# 03_MCU.net
KiCad netlist of a schematic drawn in Altium Designer
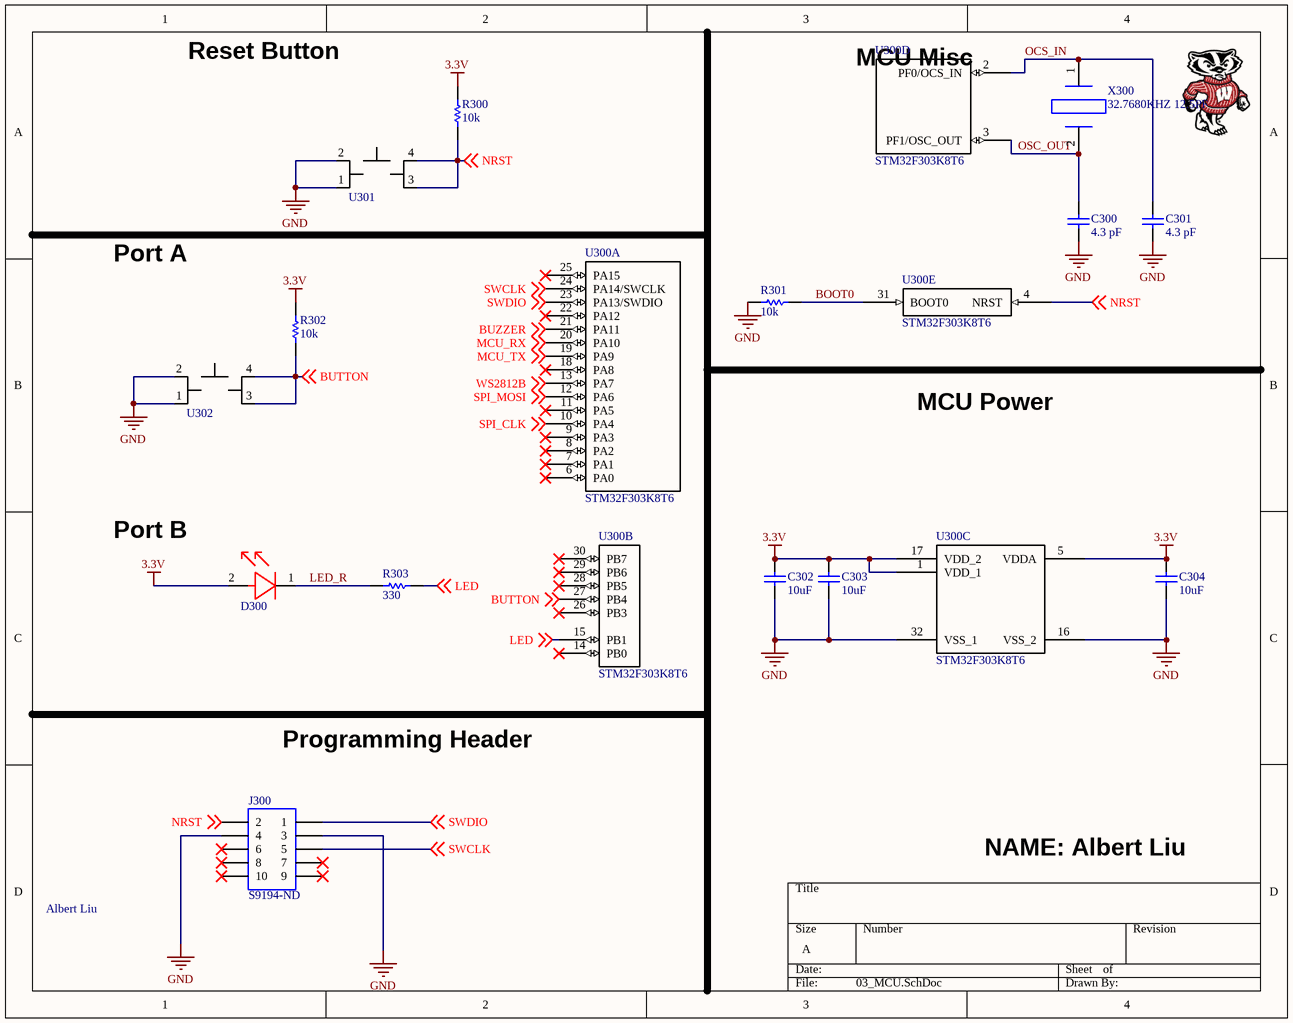
[diagram p0: 03_MCU.SchDoc]

(export (version "E")
  (design (tool "Eeschema 10.0.6"))
  (components
    (comp (ref "C300")
      (value "CAP_0805_P_004.30")
      (footprint "CAP_0805")
      (description "CAP CER 4.3PF 100V NP0 0805")
      (fields
        (field (name "MANUFACTURER") "Kyocera AVX")
        (field (name "MANUFACTURER PART NUMBER") "08051A4R3CAT2A")
        (field (name "CAPACITANCE VALUE") "4.3 pF")
      )
      (libsource (lib "ece315-S20") (part "CAP_0805_P_004.30"))
    )
    (comp (ref "C301")
      (value "CAP_0805_P_004.30")
      (footprint "CAP_0805")
      (description "CAP CER 4.3PF 100V NP0 0805")
      (fields
        (field (name "MANUFACTURER") "Kyocera AVX")
        (field (name "MANUFACTURER PART NUMBER") "08051A4R3CAT2A")
        (field (name "CAPACITANCE VALUE") "4.3 pF")
      )
      (libsource (lib "ece315-S20") (part "CAP_0805_P_004.30"))
    )
    (comp (ref "C302")
      (value "10uF")
      (footprint "CAP_0805")
      (description "CAP CER 10UF 16V X7R 0805")
      (fields
        (field (name "MANUFACTURER") "Samsung")
        (field (name "MANUFACTURER PART NUMBER") "CL21A106KPCLQNC")
        (field (name "CAPACITANCE") "10uF")
      )
      (libsource (lib "ece315-S20") (part "CAP_0805_U_010.00"))
    )
    (comp (ref "C303")
      (value "10uF")
      (footprint "CAP_0805")
      (description "CAP CER 10UF 16V X7R 0805")
      (fields
        (field (name "MANUFACTURER") "Samsung")
        (field (name "MANUFACTURER PART NUMBER") "CL21A106KPCLQNC")
        (field (name "CAPACITANCE") "10uF")
      )
      (libsource (lib "ece315-S20") (part "CAP_0805_U_010.00"))
    )
    (comp (ref "C304")
      (value "10uF")
      (footprint "CAP_0805")
      (description "CAP CER 10UF 16V X7R 0805")
      (fields
        (field (name "MANUFACTURER") "Samsung")
        (field (name "MANUFACTURER PART NUMBER") "CL21A106KPCLQNC")
        (field (name "CAPACITANCE") "10uF")
      )
      (libsource (lib "ece315-S20") (part "CAP_0805_U_010.00"))
    )
    (comp (ref "D300")
      (value "LED_RED_0805.1")
      (footprint "LED_RED_0805")
      (description "LED SUPER RED CLR THIN 0805 SMD")
      (fields
        (field (name "MANUFACTURER") "Vishay / Lite-On")
        (field (name "MANUFACTURER PART NUMBER") "LTST-C171KRKT")
      )
      (libsource (lib "ece315-S20") (part "LED_RED_0805.1"))
    )
    (comp (ref "J300")
      (value "SFH11-PBPC-D05-ST-BK")
      (footprint "SFH11-PBPC-D05-ST-BK")
      (description "CONN HDR 10POS 0.1 GOLD PCB")
      (fields (field (name "SUPPLIER PART NUMBER 1") "S9194-ND"))
      (libsource (lib "ece315-S20") (part "SFH11-PBPC-D05-ST-BK"))
    )
    (comp (ref "R300")
      (value "10K")
      (footprint "RES_0805")
      (description "RES SMD 10K OHM 1% 1/8W 0805")
      (fields
        (field (name "MANUFACTURER") "Panasonic / Panasonic ECG")
        (field (name "MANUFACTURER PART NUMBER") "ERJ-6ENF1002V")
        (field (name "RESISTANCE") "10k")
      )
      (libsource (lib "ece315-S20") (part "RES_0805_K_010.00"))
    )
    (comp (ref "R301")
      (value "10K")
      (footprint "RES_0805")
      (description "RES SMD 10K OHM 1% 1/8W 0805")
      (fields
        (field (name "MANUFACTURER") "Panasonic / Panasonic ECG")
        (field (name "MANUFACTURER PART NUMBER") "ERJ-6ENF1002V")
        (field (name "RESISTANCE") "10k")
      )
      (libsource (lib "ece315-S20") (part "RES_0805_K_010.00"))
    )
    (comp (ref "R302")
      (value "10K")
      (footprint "RES_0805")
      (description "RES SMD 10K OHM 1% 1/8W 0805")
      (fields
        (field (name "MANUFACTURER") "Panasonic / Panasonic ECG")
        (field (name "MANUFACTURER PART NUMBER") "ERJ-6ENF1002V")
        (field (name "RESISTANCE") "10k")
      )
      (libsource (lib "ece315-S20") (part "RES_0805_K_010.00"))
    )
    (comp (ref "R303")
      (value "330")
      (footprint "RES_0805")
      (description "RES SMD 330 OHM 1% 1/8W 0805")
      (fields
        (field (name "MANUFACTURER") "Panasonic / Panasonic ECG")
        (field (name "MANUFACTURER PART NUMBER") "ERJ-6ENF3300V")
        (field (name "RESISTANCE") "330")
      )
      (libsource (lib "ece315-S20") (part "RES_0805_R_330.00"))
    )
    (comp (ref "U300")
      (value "IC_STM32F303K8T6")
      (footprint "LQFP32")
      (description "ARM® Cortex®-M4 STM32 F3 Microcontroller IC 32-Bit 72MHz 64KB (64K x 8) FLASH 32-LQFP (7x7)")
      (fields
        (field (name "MANUFACTURER") "STMicroelectronics")
        (field (name "MANUFACTURER PART NUMBER") "STM32F303K8T6")
      )
      (libsource (lib "ece315-S20") (part "IC_STM32F303K8T6"))
    )
    (comp (ref "U301")
      (value "SWITCH_6mm_6mm_smd")
      (footprint "SWITCH_6mm_6mm_smd")
      (description "SWITCH TACTILE SPST-NO 0.05A 12V")
      (fields
        (field (name "MANUFACTURER") "C&K Components")
        (field (name "MANUFACTURER PART NUMBER") "PTS645SH50SMTR92 LFS")
      )
      (libsource (lib "ece315-S20") (part "SWITCH_6mm_6mm_smd"))
    )
    (comp (ref "U302")
      (value "SWITCH_6mm_6mm_smd")
      (footprint "SWITCH_6mm_6mm_smd")
      (description "SWITCH TACTILE SPST-NO 0.05A 12V")
      (fields
        (field (name "MANUFACTURER") "C&K Components")
        (field (name "MANUFACTURER PART NUMBER") "PTS645SH50SMTR92 LFS")
      )
      (libsource (lib "ece315-S20") (part "SWITCH_6mm_6mm_smd"))
    )
    (comp (ref "X300")
      (value "32.7680KHZ 12.5PF")
      (footprint "NX3215SA-32.768K-STD-MUA-8")
      (description "CRYSTAL 32.768KHZ 12.5PF SMD")
      (fields
        (field (name "MANUFACTURER") "Nihon Dempa Kogyo (NDK)")
        (field (name "MANUFACTURER PART NUMBER") "NX3215SA-32.768K-STD-MUA-8")
      )
      (libsource (lib "ece315-S20") (part "CRYSTAL_NX3215SA-32.768K"))
    )
  )
  (nets
    (net (code "1") (name "/BOOT0") (class "Default")
      (node (ref "R301") (pin "2") (pinfunction "2_2") (pintype "passive"))
      (node (ref "U300") (pin "31") (pinfunction "BOOT0_31") (pintype "input"))
    )
    (net (code "2") (name "/LED_R") (class "Default")
      (node (ref "D300") (pin "1") (pinfunction "Cathode_1") (pintype "passive"))
      (node (ref "R303") (pin "1") (pinfunction "1_1") (pintype "passive"))
    )
    (net (code "3") (name "/OCS_IN") (class "Default")
      (node (ref "C301") (pin "2") (pinfunction "2_2") (pintype "passive"))
      (node (ref "U300") (pin "2") (pinfunction "PF0/OCS_IN_2") (pintype "bidirectional"))
      (node (ref "X300") (pin "1") (pinfunction "1_1") (pintype "passive"))
    )
    (net (code "4") (name "/OSC_OUT") (class "Default")
      (node (ref "C300") (pin "2") (pinfunction "2_2") (pintype "passive"))
      (node (ref "U300") (pin "3") (pinfunction "PF1/OSC_OUT_3") (pintype "bidirectional"))
      (node (ref "X300") (pin "2") (pinfunction "2_2") (pintype "passive"))
    )
    (net (code "5") (name "3.3V") (class "Default")
      (node (ref "C302") (pin "2") (pinfunction "2_2") (pintype "passive"))
      (node (ref "C303") (pin "2") (pinfunction "2_2") (pintype "passive"))
      (node (ref "C304") (pin "2") (pinfunction "2_2") (pintype "passive"))
      (node (ref "D300") (pin "2") (pinfunction "Anode_2") (pintype "passive"))
      (node (ref "R300") (pin "2") (pinfunction "2_2") (pintype "passive"))
      (node (ref "R302") (pin "2") (pinfunction "2_2") (pintype "passive"))
      (node (ref "U300") (pin "1") (pinfunction "VDD_1_1") (pintype "power_in"))
      (node (ref "U300") (pin "17") (pinfunction "VDD_2_17") (pintype "power_in"))
      (node (ref "U300") (pin "5") (pinfunction "VDDA_5") (pintype "power_in"))
    )
    (net (code "6") (name "BUTTON") (class "Default")
      (node (ref "R302") (pin "1") (pinfunction "1_1") (pintype "passive"))
      (node (ref "U300") (pin "27") (pinfunction "PB4_27") (pintype "bidirectional"))
      (node (ref "U302") (pin "3") (pinfunction "3_3") (pintype "passive"))
      (node (ref "U302") (pin "4") (pinfunction "VCCIO_4") (pintype "passive"))
    )
    (net (code "7") (name "BUZZER") (class "Default")
      (node (ref "U300") (pin "21") (pinfunction "PA11_21") (pintype "bidirectional"))
    )
    (net (code "8") (name "GND") (class "Default")
      (node (ref "C300") (pin "1") (pinfunction "1_1") (pintype "passive"))
      (node (ref "C301") (pin "1") (pinfunction "1_1") (pintype "passive"))
      (node (ref "C302") (pin "1") (pinfunction "1_1") (pintype "passive"))
      (node (ref "C303") (pin "1") (pinfunction "1_1") (pintype "passive"))
      (node (ref "C304") (pin "1") (pinfunction "1_1") (pintype "passive"))
      (node (ref "J300") (pin "3") (pinfunction "3_3") (pintype "passive"))
      (node (ref "J300") (pin "4") (pinfunction "4_4") (pintype "passive"))
      (node (ref "R301") (pin "1") (pinfunction "1_1") (pintype "passive"))
      (node (ref "U300") (pin "16") (pinfunction "VSS_2_16") (pintype "power_in"))
      (node (ref "U300") (pin "32") (pinfunction "VSS_1_32") (pintype "power_in"))
      (node (ref "U301") (pin "1") (pinfunction "1_1") (pintype "passive"))
      (node (ref "U301") (pin "2") (pinfunction "2_2") (pintype "passive"))
      (node (ref "U302") (pin "1") (pinfunction "1_1") (pintype "passive"))
      (node (ref "U302") (pin "2") (pinfunction "2_2") (pintype "passive"))
    )
    (net (code "9") (name "LED") (class "Default")
      (node (ref "R303") (pin "2") (pinfunction "2_2") (pintype "passive"))
      (node (ref "U300") (pin "15") (pinfunction "PB1_15") (pintype "bidirectional"))
    )
    (net (code "10") (name "MCU_RX") (class "Default")
      (node (ref "U300") (pin "20") (pinfunction "PA10_20") (pintype "bidirectional"))
    )
    (net (code "11") (name "MCU_TX") (class "Default")
      (node (ref "U300") (pin "19") (pinfunction "PA9_19") (pintype "bidirectional"))
    )
    (net (code "12") (name "NRST") (class "Default")
      (node (ref "J300") (pin "2") (pinfunction "2_2") (pintype "passive"))
      (node (ref "R300") (pin "1") (pinfunction "1_1") (pintype "passive"))
      (node (ref "U300") (pin "4") (pinfunction "NRST_4") (pintype "input"))
      (node (ref "U301") (pin "3") (pinfunction "3_3") (pintype "passive"))
      (node (ref "U301") (pin "4") (pinfunction "VCCIO_4") (pintype "passive"))
    )
    (net (code "13") (name "SPI_CLK") (class "Default")
      (node (ref "U300") (pin "10") (pinfunction "PA4_10") (pintype "bidirectional"))
    )
    (net (code "14") (name "SPI_MOSI") (class "Default")
      (node (ref "U300") (pin "12") (pinfunction "PA6_12") (pintype "bidirectional"))
    )
    (net (code "15") (name "SWCLK") (class "Default")
      (node (ref "J300") (pin "5") (pinfunction "5_5") (pintype "passive"))
      (node (ref "U300") (pin "24") (pinfunction "PA14/SWCLK_24") (pintype "bidirectional"))
    )
    (net (code "16") (name "SWDIO") (class "Default")
      (node (ref "J300") (pin "1") (pinfunction "1_1") (pintype "passive"))
      (node (ref "U300") (pin "23") (pinfunction "PA13/SWDIO_23") (pintype "bidirectional"))
    )
    (net (code "17") (name "WS2812B") (class "Default")
      (node (ref "U300") (pin "13") (pinfunction "PA7_13") (pintype "bidirectional"))
    )
    (net (code "18") (name "unconnected-(J300-Pad6)") (class "Default")
      (node (ref "J300") (pin "6") (pinfunction "6_6") (pintype "passive+no_connect"))
    )
    (net (code "19") (name "unconnected-(J300-Pad7)") (class "Default")
      (node (ref "J300") (pin "7") (pinfunction "7_7") (pintype "passive+no_connect"))
    )
    (net (code "20") (name "unconnected-(J300-Pad8)") (class "Default")
      (node (ref "J300") (pin "8") (pinfunction "8_8") (pintype "passive+no_connect"))
    )
    (net (code "21") (name "unconnected-(J300-Pad9)") (class "Default")
      (node (ref "J300") (pin "9") (pinfunction "9_9") (pintype "passive+no_connect"))
    )
    (net (code "22") (name "unconnected-(J300-Pad10)") (class "Default")
      (node (ref "J300") (pin "10") (pinfunction "10_10") (pintype "passive+no_connect"))
    )
    (net (code "23") (name "unconnected-(U300A-PA0-Pad6)") (class "Default")
      (node (ref "U300") (pin "6") (pinfunction "PA0_6") (pintype "bidirectional+no_connect"))
    )
    (net (code "24") (name "unconnected-(U300A-PA1-Pad7)") (class "Default")
      (node (ref "U300") (pin "7") (pinfunction "PA1_7") (pintype "bidirectional+no_connect"))
    )
    (net (code "25") (name "unconnected-(U300A-PA2-Pad8)") (class "Default")
      (node (ref "U300") (pin "8") (pinfunction "PA2_8") (pintype "bidirectional+no_connect"))
    )
    (net (code "26") (name "unconnected-(U300A-PA3-Pad9)") (class "Default")
      (node (ref "U300") (pin "9") (pinfunction "PA3_9") (pintype "bidirectional+no_connect"))
    )
    (net (code "27") (name "unconnected-(U300A-PA5-Pad11)") (class "Default")
      (node (ref "U300") (pin "11") (pinfunction "PA5_11") (pintype "bidirectional+no_connect"))
    )
    (net (code "28") (name "unconnected-(U300A-PA8-Pad18)") (class "Default")
      (node (ref "U300") (pin "18") (pinfunction "PA8_18") (pintype "bidirectional+no_connect"))
    )
    (net (code "29") (name "unconnected-(U300A-PA12-Pad22)") (class "Default")
      (node (ref "U300") (pin "22") (pinfunction "PA12_22") (pintype "bidirectional+no_connect"))
    )
    (net (code "30") (name "unconnected-(U300A-PA15-Pad25)") (class "Default")
      (node (ref "U300") (pin "25") (pinfunction "PA15_25") (pintype "bidirectional+no_connect"))
    )
    (net (code "31") (name "unconnected-(U300B-PB0-Pad14)") (class "Default")
      (node (ref "U300") (pin "14") (pinfunction "PB0_14") (pintype "bidirectional+no_connect"))
    )
    (net (code "32") (name "unconnected-(U300B-PB3-Pad26)") (class "Default")
      (node (ref "U300") (pin "26") (pinfunction "PB3_26") (pintype "bidirectional+no_connect"))
    )
    (net (code "33") (name "unconnected-(U300B-PB5-Pad28)") (class "Default")
      (node (ref "U300") (pin "28") (pinfunction "PB5_28") (pintype "bidirectional+no_connect"))
    )
    (net (code "34") (name "unconnected-(U300B-PB6-Pad29)") (class "Default")
      (node (ref "U300") (pin "29") (pinfunction "PB6_29") (pintype "bidirectional+no_connect"))
    )
    (net (code "35") (name "unconnected-(U300B-PB7-Pad30)") (class "Default")
      (node (ref "U300") (pin "30") (pinfunction "PB7_30") (pintype "bidirectional+no_connect"))
    )
  )
)
